# 3w-rgb-led-connector-mk-1_0.net
KiCad netlist of a schematic drawn in EAGLE
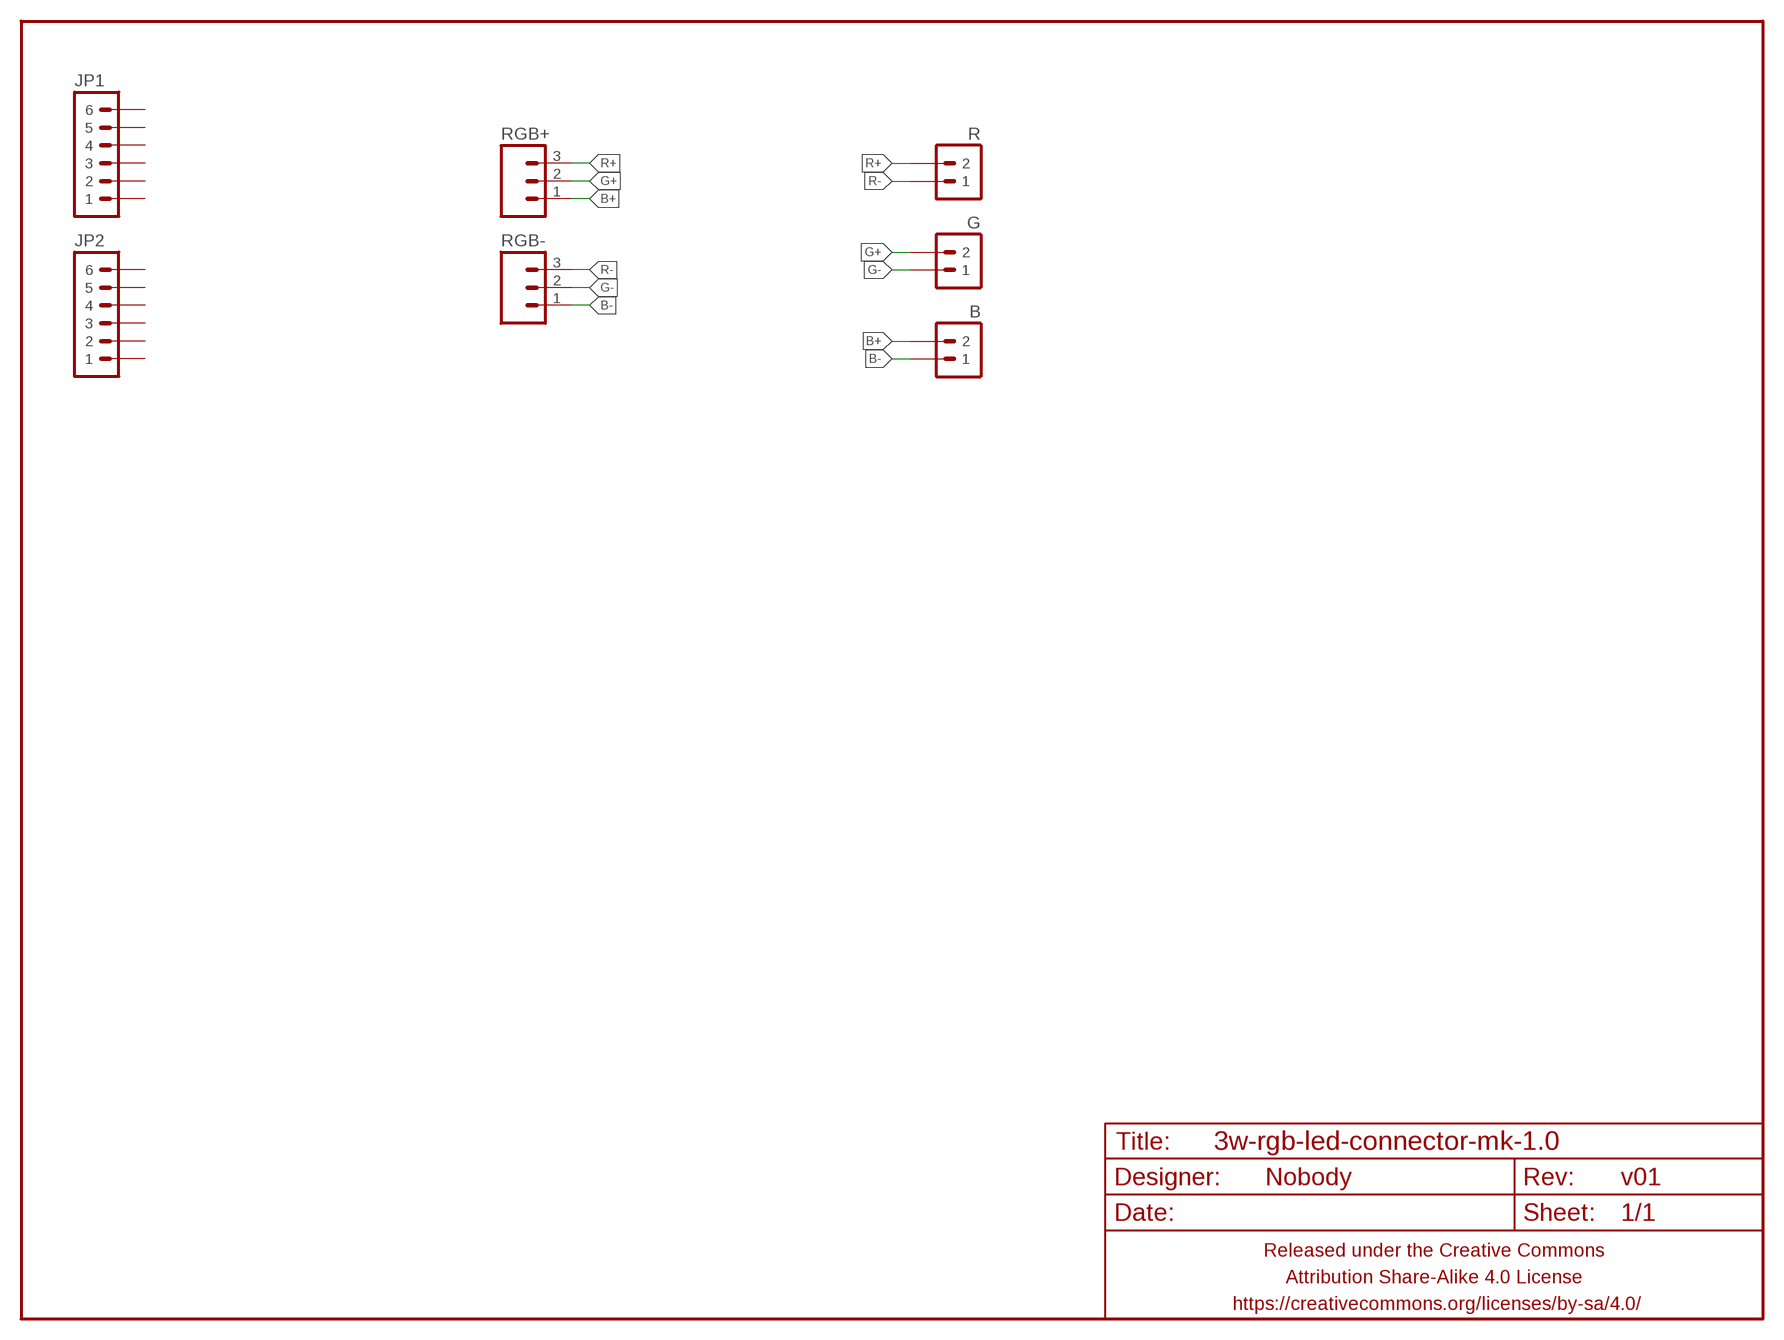
[diagram p0: schematic, sheet 1]

(export (version "E")
  (design (tool "Eeschema 10.0.6"))
  (components
    (comp (ref "B")
      (value "M023.5MM-NO_SILK")
      (footprint "eagle-import:SCREWTERMINAL-3.5MM-2-NS")
      (libsource (lib "eagle-import") (part "M023.5MM-NO_SILK"))
    )
    (comp (ref "FRAME1")
      (value "FRAME-LETTERNO_PACKAGE")
      (footprint "eagle-import:DUMMY")
      (fields (field (name "DESIGNER") "Nobody"))
      (libsource (lib "eagle-import") (part "FRAME-LETTERNO_PACKAGE"))
    )
    (comp (ref "G")
      (value "M023.5MM-NO_SILK")
      (footprint "eagle-import:SCREWTERMINAL-3.5MM-2-NS")
      (libsource (lib "eagle-import") (part "M023.5MM-NO_SILK"))
    )
    (comp (ref "JP1")
      (value "M06SIP")
      (footprint "eagle-import:1X06")
      (libsource (lib "eagle-import") (part "M06SIP"))
    )
    (comp (ref "JP2")
      (value "M06SIP")
      (footprint "eagle-import:1X06")
      (libsource (lib "eagle-import") (part "M06SIP"))
    )
    (comp (ref "R")
      (value "M023.5MM-NO_SILK")
      (footprint "eagle-import:SCREWTERMINAL-3.5MM-2-NS")
      (libsource (lib "eagle-import") (part "M023.5MM-NO_SILK"))
    )
    (comp (ref "RGB+")
      (value "M03JST-XH-RA-PTH")
      (footprint "eagle-import:JST-3-XH-RA-PTH")
      (libsource (lib "eagle-import") (part "M03JST-XH-RA-PTH"))
    )
    (comp (ref "RGB-")
      (value "M03JST-XH-RA-PTH")
      (footprint "eagle-import:JST-3-XH-RA-PTH")
      (libsource (lib "eagle-import") (part "M03JST-XH-RA-PTH"))
    )
  )
  (nets
    (net (code "1") (name "B+") (class "Default")
      (node (ref "B") (pin "2") (pinfunction "2_2") (pintype "passive"))
      (node (ref "RGB+") (pin "1") (pinfunction "1_1") (pintype "passive"))
    )
    (net (code "2") (name "B-") (class "Default")
      (node (ref "B") (pin "1") (pinfunction "1_1") (pintype "passive"))
      (node (ref "RGB-") (pin "1") (pinfunction "1_1") (pintype "passive"))
    )
    (net (code "3") (name "G+") (class "Default")
      (node (ref "G") (pin "2") (pinfunction "2_2") (pintype "passive"))
      (node (ref "RGB+") (pin "2") (pinfunction "2_2") (pintype "passive"))
    )
    (net (code "4") (name "G-") (class "Default")
      (node (ref "G") (pin "1") (pinfunction "1_1") (pintype "passive"))
      (node (ref "RGB-") (pin "2") (pinfunction "2_2") (pintype "passive"))
    )
    (net (code "5") (name "R+") (class "Default")
      (node (ref "R") (pin "2") (pinfunction "2_2") (pintype "passive"))
      (node (ref "RGB+") (pin "3") (pinfunction "3_3") (pintype "passive"))
    )
    (net (code "6") (name "R-") (class "Default")
      (node (ref "R") (pin "1") (pinfunction "1_1") (pintype "passive"))
      (node (ref "RGB-") (pin "3") (pinfunction "3_3") (pintype "passive"))
    )
    (net (code "7") (name "unconnected-(JP1-Pad1)") (class "Default")
      (node (ref "JP1") (pin "1") (pinfunction "1_1") (pintype "passive"))
    )
    (net (code "8") (name "unconnected-(JP1-Pad2)") (class "Default")
      (node (ref "JP1") (pin "2") (pinfunction "2_2") (pintype "passive"))
    )
    (net (code "9") (name "unconnected-(JP1-Pad3)") (class "Default")
      (node (ref "JP1") (pin "3") (pinfunction "3_3") (pintype "passive"))
    )
    (net (code "10") (name "unconnected-(JP1-Pad4)") (class "Default")
      (node (ref "JP1") (pin "4") (pinfunction "4_4") (pintype "passive"))
    )
    (net (code "11") (name "unconnected-(JP1-Pad5)") (class "Default")
      (node (ref "JP1") (pin "5") (pinfunction "5_5") (pintype "passive"))
    )
    (net (code "12") (name "unconnected-(JP1-Pad6)") (class "Default")
      (node (ref "JP1") (pin "6") (pinfunction "6_6") (pintype "passive"))
    )
    (net (code "13") (name "unconnected-(JP2-Pad1)") (class "Default")
      (node (ref "JP2") (pin "1") (pinfunction "1_1") (pintype "passive"))
    )
    (net (code "14") (name "unconnected-(JP2-Pad2)") (class "Default")
      (node (ref "JP2") (pin "2") (pinfunction "2_2") (pintype "passive"))
    )
    (net (code "15") (name "unconnected-(JP2-Pad3)") (class "Default")
      (node (ref "JP2") (pin "3") (pinfunction "3_3") (pintype "passive"))
    )
    (net (code "16") (name "unconnected-(JP2-Pad4)") (class "Default")
      (node (ref "JP2") (pin "4") (pinfunction "4_4") (pintype "passive"))
    )
    (net (code "17") (name "unconnected-(JP2-Pad5)") (class "Default")
      (node (ref "JP2") (pin "5") (pinfunction "5_5") (pintype "passive"))
    )
    (net (code "18") (name "unconnected-(JP2-Pad6)") (class "Default")
      (node (ref "JP2") (pin "6") (pinfunction "6_6") (pintype "passive"))
    )
  )
)
